# threestate_driver.net
KiCad netlist of a schematic drawn in EAGLE
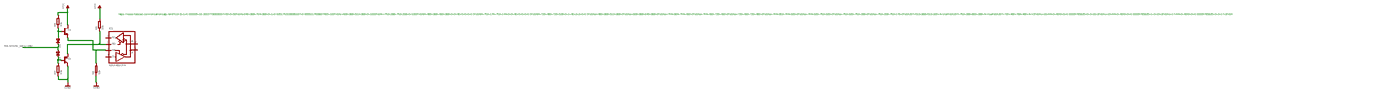
[diagram p0: schematic, sheet 1, overview]
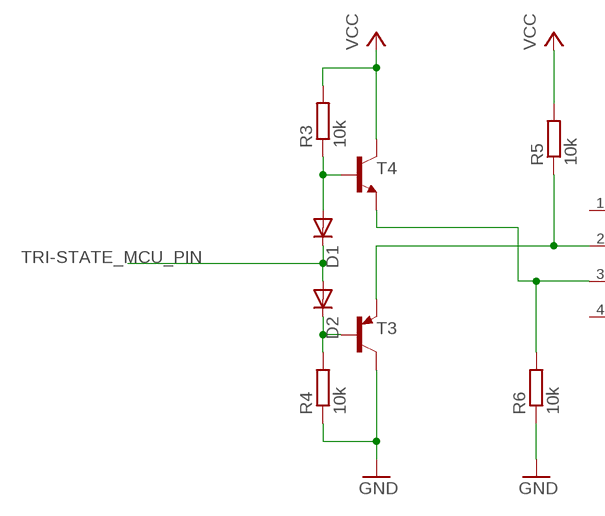
[diagram p1: schematic, sheet 1, part 1 of 4]
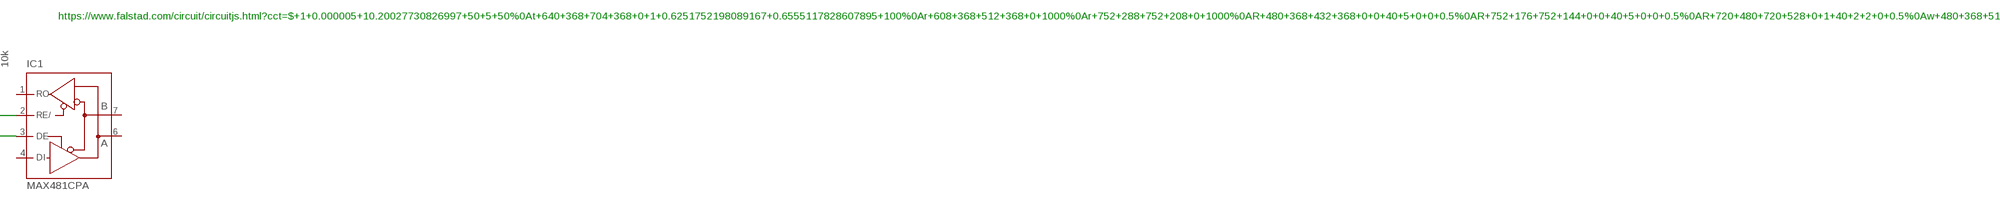
[diagram p2: schematic, sheet 1, part 2 of 4]
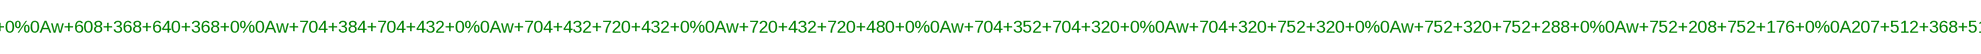
[diagram p3: schematic, sheet 1, part 3 of 4]
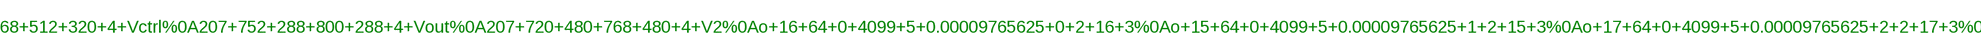
[diagram p4: schematic, sheet 1, part 4 of 4]

(export (version "E")
  (design (tool "Eeschema 10.0.6"))
  (components
    (comp (ref "D1")
      (value "1N4148DO35-10")
      (footprint "eagle-import:DO35-10")
      (libsource (lib "eagle-import") (part "1N4148DO35-10"))
    )
    (comp (ref "D2")
      (value "1N4148DO35-10")
      (footprint "eagle-import:DO35-10")
      (libsource (lib "eagle-import") (part "1N4148DO35-10"))
    )
    (comp (ref "IC1")
      (value "MAX481CPA")
      (footprint "eagle-import:DIL08")
      (fields (field (name "MPN") "MAX481CPA+"))
      (libsource (lib "eagle-import") (part "MAX481CPA"))
    )
    (comp (ref "R3")
      (value "10k")
      (footprint "eagle-import:R0805")
      (libsource (lib "eagle-import") (part "R-EU_R0805"))
    )
    (comp (ref "R4")
      (value "10k")
      (footprint "eagle-import:R0805")
      (libsource (lib "eagle-import") (part "R-EU_R0805"))
    )
    (comp (ref "R5")
      (value "10k")
      (footprint "eagle-import:R0805")
      (libsource (lib "eagle-import") (part "R-EU_R0805"))
    )
    (comp (ref "R6")
      (value "10k")
      (footprint "eagle-import:R0805")
      (libsource (lib "eagle-import") (part "R-EU_R0805"))
    )
    (comp (ref "T3")
      (value "-PNP-TO92")
      (footprint "eagle-import:TO92")
      (libsource (lib "eagle-import") (part "-PNP-TO92"))
    )
    (comp (ref "T4")
      (value "-NPN-TO92")
      (footprint "eagle-import:TO92")
      (libsource (lib "eagle-import") (part "-NPN-TO92"))
    )
  )
  (nets
    (net (code "1") (name "/TRI-STATE_MCU_PIN") (class "Default")
      (node (ref "D1") (pin "C") (pinfunction "C_C") (pintype "passive"))
      (node (ref "D2") (pin "A") (pinfunction "A_A") (pintype "passive"))
    )
    (net (code "2") (name "GND") (class "Default")
      (node (ref "R4") (pin "1") (pinfunction "1_1") (pintype "passive"))
      (node (ref "R6") (pin "1") (pinfunction "1_1") (pintype "passive"))
      (node (ref "T3") (pin "3") (pinfunction "C_3") (pintype "passive"))
    )
    (net (code "3") (name "Net-(IC1A-DE)") (class "Default")
      (node (ref "IC1") (pin "3") (pinfunction "DE_3") (pintype "input"))
      (node (ref "R6") (pin "2") (pinfunction "2_2") (pintype "passive"))
      (node (ref "T4") (pin "1") (pinfunction "E_1") (pintype "passive"))
    )
    (net (code "4") (name "Net-(IC1A-RE{slash})") (class "Default")
      (node (ref "IC1") (pin "2") (pinfunction "RE/_2") (pintype "input"))
      (node (ref "R5") (pin "1") (pinfunction "1_1") (pintype "passive"))
      (node (ref "T3") (pin "1") (pinfunction "E_1") (pintype "passive"))
    )
    (net (code "5") (name "Net-(T3-B)") (class "Default")
      (node (ref "D2") (pin "C") (pinfunction "C_C") (pintype "passive"))
      (node (ref "R4") (pin "2") (pinfunction "2_2") (pintype "passive"))
      (node (ref "T3") (pin "2") (pinfunction "B_2") (pintype "passive"))
    )
    (net (code "6") (name "Net-(T4-B)") (class "Default")
      (node (ref "D1") (pin "A") (pinfunction "A_A") (pintype "passive"))
      (node (ref "R3") (pin "1") (pinfunction "1_1") (pintype "passive"))
      (node (ref "T4") (pin "2") (pinfunction "B_2") (pintype "passive"))
    )
    (net (code "7") (name "VCC") (class "Default")
      (node (ref "R3") (pin "2") (pinfunction "2_2") (pintype "passive"))
      (node (ref "R5") (pin "2") (pinfunction "2_2") (pintype "passive"))
      (node (ref "T4") (pin "3") (pinfunction "C_3") (pintype "passive"))
    )
    (net (code "8") (name "unconnected-(IC1A-A-Pad6)") (class "Default")
      (node (ref "IC1") (pin "6") (pinfunction "A_6") (pintype "passive"))
    )
    (net (code "9") (name "unconnected-(IC1A-B-Pad7)") (class "Default")
      (node (ref "IC1") (pin "7") (pinfunction "B_7") (pintype "passive"))
    )
    (net (code "10") (name "unconnected-(IC1A-DI-Pad4)") (class "Default")
      (node (ref "IC1") (pin "4") (pinfunction "DI_4") (pintype "input"))
    )
    (net (code "11") (name "unconnected-(IC1A-RO-Pad1)") (class "Default")
      (node (ref "IC1") (pin "1") (pinfunction "RO_1") (pintype "output"))
    )
  )
)
